# SCH_06_Filter.net
KiCad netlist of a schematic drawn in Altium Designer
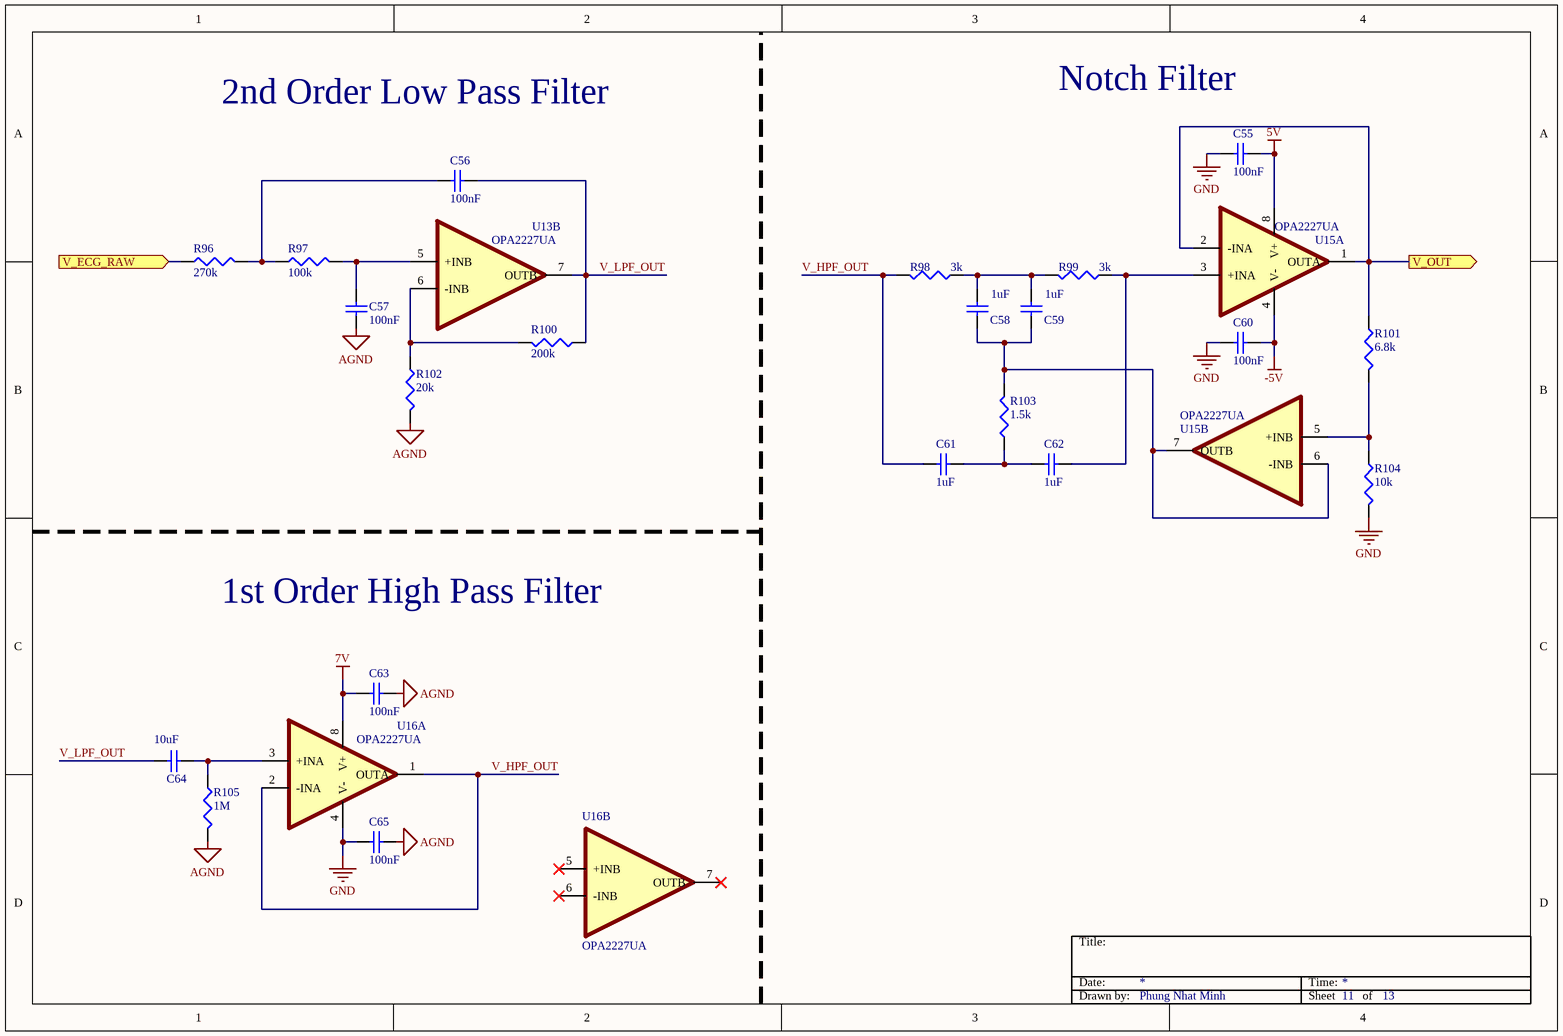
[diagram p0: SCH_06_Filter.SchDoc]

(export (version "E")
  (design (tool "Eeschema 10.0.6"))
  (components
    (comp (ref "C55")
      (value "100nF")
      (footprint "WCAP-CSGP_0603_L1.6W0.8H0.8_Reflow")
      (description "WCAP-CSGP Multilayer Ceramic Chip Capacitor, General Purpose, size 0603, X7R, 100nF, 16VDC")
      (fields
        (field (name "MANUFACTURER PART NUMBER") "885012206046")
        (field (name "MANUFACTURER") "Wurth Elektronik")
      )
      (libsource (lib "Altium_WCAP-CSGP (rev24b)") (part "885012206046"))
    )
    (comp (ref "C56")
      (value "100nF")
      (footprint "WCAP-CSGP_0603_L1.6W0.8H0.8_Reflow")
      (description "WCAP-CSGP Multilayer Ceramic Chip Capacitor, General Purpose, size 0603, X7R, 100nF, 50VDC")
      (fields
        (field (name "MANUFACTURER PART NUMBER") "885012206095")
        (field (name "MANUFACTURER") "Wurth Elektronik")
      )
      (libsource (lib "Altium_WCAP-CSGP (rev24b)") (part "885012206095"))
    )
    (comp (ref "C57")
      (value "100nF")
      (footprint "WCAP-CSGP_0603_L1.6W0.8H0.8_Reflow")
      (description "WCAP-CSGP Multilayer Ceramic Chip Capacitor, General Purpose, size 0603, X7R, 100nF, 50VDC")
      (fields
        (field (name "MANUFACTURER PART NUMBER") "885012206095")
        (field (name "MANUFACTURER") "Wurth Elektronik")
      )
      (libsource (lib "Altium_WCAP-CSGP (rev24b)") (part "885012206095"))
    )
    (comp (ref "C58")
      (value "1uF")
      (footprint "WCAP-CSGP_0603_L1.6W0.8H0.8_Reflow")
      (description "WCAP-CSGP Multilayer Ceramic Chip Capacitor, General Purpose, size 0603, X5R, 1uF, 25VDC")
      (fields
        (field (name "MANUFACTURER PART NUMBER") "885012106022")
        (field (name "MANUFACTURER") "Wurth Elektronik")
      )
      (libsource (lib "Altium_WCAP-CSGP (rev24b)") (part "885012106022"))
    )
    (comp (ref "C59")
      (value "1uF")
      (footprint "WCAP-CSGP_0603_L1.6W0.8H0.8_Reflow")
      (description "WCAP-CSGP Multilayer Ceramic Chip Capacitor, General Purpose, size 0603, X5R, 1uF, 25VDC")
      (fields
        (field (name "MANUFACTURER PART NUMBER") "885012106022")
        (field (name "MANUFACTURER") "Wurth Elektronik")
      )
      (libsource (lib "Altium_WCAP-CSGP (rev24b)") (part "885012106022"))
    )
    (comp (ref "C60")
      (value "100nF")
      (footprint "WCAP-CSGP_0603_L1.6W0.8H0.8_Reflow")
      (description "WCAP-CSGP Multilayer Ceramic Chip Capacitor, General Purpose, size 0603, X7R, 100nF, 16VDC")
      (fields
        (field (name "MANUFACTURER PART NUMBER") "885012206046")
        (field (name "MANUFACTURER") "Wurth Elektronik")
      )
      (libsource (lib "Altium_WCAP-CSGP (rev24b)") (part "885012206046"))
    )
    (comp (ref "C61")
      (value "1uF")
      (footprint "WCAP-CSGP_0603_L1.6W0.8H0.8_Reflow")
      (description "WCAP-CSGP Multilayer Ceramic Chip Capacitor, General Purpose, size 0603, X5R, 1uF, 25VDC")
      (fields
        (field (name "MANUFACTURER PART NUMBER") "885012106022")
        (field (name "MANUFACTURER") "Wurth Elektronik")
      )
      (libsource (lib "Altium_WCAP-CSGP (rev24b)") (part "885012106022"))
    )
    (comp (ref "C62")
      (value "1uF")
      (footprint "WCAP-CSGP_0603_L1.6W0.8H0.8_Reflow")
      (description "WCAP-CSGP Multilayer Ceramic Chip Capacitor, General Purpose, size 0603, X5R, 1uF, 25VDC")
      (fields
        (field (name "MANUFACTURER PART NUMBER") "885012106022")
        (field (name "MANUFACTURER") "Wurth Elektronik")
      )
      (libsource (lib "Altium_WCAP-CSGP (rev24b)") (part "885012106022"))
    )
    (comp (ref "C63")
      (value "100nF")
      (footprint "WCAP-CSGP_0603_L1.6W0.8H0.8_Reflow")
      (description "WCAP-CSGP Multilayer Ceramic Chip Capacitor, General Purpose, size 0603, X7R, 100nF, 50VDC")
      (fields
        (field (name "MANUFACTURER PART NUMBER") "885012206095")
        (field (name "MANUFACTURER") "Wurth Elektronik")
      )
      (libsource (lib "Altium_WCAP-CSGP (rev24b)") (part "885012206095"))
    )
    (comp (ref "C64")
      (value "10uF")
      (footprint "WCAP-CSGP_0603_L1.6W0.8H0.8_Reflow")
      (description "WCAP-CSGP Multilayer Ceramic Chip Capacitor, General Purpose, size 0603, X5R, 10uF, 25VDC")
      (fields
        (field (name "MANUFACTURER PART NUMBER") "885012106031")
        (field (name "MANUFACTURER") "Wurth Elektronik")
      )
      (libsource (lib "Altium_WCAP-CSGP (rev24b)") (part "885012106031"))
    )
    (comp (ref "C65")
      (value "100nF")
      (footprint "WCAP-CSGP_0603_L1.6W0.8H0.8_Reflow")
      (description "WCAP-CSGP Multilayer Ceramic Chip Capacitor, General Purpose, size 0603, X7R, 100nF, 50VDC")
      (fields
        (field (name "MANUFACTURER PART NUMBER") "885012206095")
        (field (name "MANUFACTURER") "Wurth Elektronik")
      )
      (libsource (lib "Altium_WCAP-CSGP (rev24b)") (part "885012206095"))
    )
    (comp (ref "R96")
      (value "270k")
      (footprint "WRIS-PSMB_0603_L1.6W0.8H0.35")
      (description "WRIS-PSMB Metal Plate Resistor, SMT, size 0603, 0.33W, 5mΩ, +/-1%")
      (fields
        (field (name "MANUFACTURER PART NUMBER") "580060716001")
        (field (name "MANUFACTURER") "Wurth Elektronik")
      )
      (libsource (lib "Altium_WRIS-PSMB (rev22a)") (part "580060716001"))
    )
    (comp (ref "R97")
      (value "100k")
      (footprint "WRIS-PSMB_0603_L1.6W0.8H0.35")
      (description "WRIS-PSMB Metal Plate Resistor, SMT, size 0603, 0.33W, 5mΩ, +/-1%")
      (fields
        (field (name "MANUFACTURER PART NUMBER") "580060716001")
        (field (name "MANUFACTURER") "Wurth Elektronik")
      )
      (libsource (lib "Altium_WRIS-PSMB (rev22a)") (part "580060716001"))
    )
    (comp (ref "R98")
      (value "3k")
      (footprint "WRIS-PSMB_0603_L1.6W0.8H0.35")
      (description "WRIS-PSMB Metal Plate Resistor, SMT, size 0603, 0.33W, 5mΩ, +/-1%")
      (fields
        (field (name "MANUFACTURER PART NUMBER") "580060716001")
        (field (name "MANUFACTURER") "Wurth Elektronik")
      )
      (libsource (lib "Altium_WRIS-PSMB (rev22a)") (part "580060716001"))
    )
    (comp (ref "R99")
      (value "3k")
      (footprint "WRIS-PSMB_0603_L1.6W0.8H0.35")
      (description "WRIS-PSMB Metal Plate Resistor, SMT, size 0603, 0.33W, 5mΩ, +/-1%")
      (fields
        (field (name "MANUFACTURER PART NUMBER") "580060716001")
        (field (name "MANUFACTURER") "Wurth Elektronik")
      )
      (libsource (lib "Altium_WRIS-PSMB (rev22a)") (part "580060716001"))
    )
    (comp (ref "R100")
      (value "200k")
      (footprint "WRIS-PSMB_0603_L1.6W0.8H0.35")
      (description "WRIS-PSMB Metal Plate Resistor, SMT, size 0603, 0.33W, 5mΩ, +/-1%")
      (fields
        (field (name "MANUFACTURER PART NUMBER") "580060716001")
        (field (name "MANUFACTURER") "Wurth Elektronik")
      )
      (libsource (lib "Altium_WRIS-PSMB (rev22a)") (part "580060716001"))
    )
    (comp (ref "R101")
      (value "6.8k")
      (footprint "WRIS-PSMB_0603_L1.6W0.8H0.35")
      (description "WRIS-PSMB Metal Plate Resistor, SMT, size 0603, 0.33W, 5mΩ, +/-1%")
      (fields
        (field (name "MANUFACTURER PART NUMBER") "580060716001")
        (field (name "MANUFACTURER") "Wurth Elektronik")
      )
      (libsource (lib "Altium_WRIS-PSMB (rev22a)") (part "580060716001"))
    )
    (comp (ref "R102")
      (value "20k")
      (footprint "WRIS-PSMB_0603_L1.6W0.8H0.35")
      (description "WRIS-PSMB Metal Plate Resistor, SMT, size 0603, 0.33W, 5mΩ, +/-1%")
      (fields
        (field (name "MANUFACTURER PART NUMBER") "580060716001")
        (field (name "MANUFACTURER") "Wurth Elektronik")
      )
      (libsource (lib "Altium_WRIS-PSMB (rev22a)") (part "580060716001"))
    )
    (comp (ref "R103")
      (value "1.5k")
      (footprint "WRIS-PSMB_0603_L1.6W0.8H0.35")
      (description "WRIS-PSMB Metal Plate Resistor, SMT, size 0603, 0.33W, 5mΩ, +/-1%")
      (fields
        (field (name "MANUFACTURER PART NUMBER") "580060716001")
        (field (name "MANUFACTURER") "Wurth Elektronik")
      )
      (libsource (lib "Altium_WRIS-PSMB (rev22a)") (part "580060716001"))
    )
    (comp (ref "R104")
      (value "10k")
      (footprint "WRIS-PSMB_0603_L1.6W0.8H0.35")
      (description "WRIS-PSMB Metal Plate Resistor, SMT, size 0603, 0.33W, 5mΩ, +/-1%")
      (fields
        (field (name "MANUFACTURER PART NUMBER") "580060716001")
        (field (name "MANUFACTURER") "Wurth Elektronik")
      )
      (libsource (lib "Altium_WRIS-PSMB (rev22a)") (part "580060716001"))
    )
    (comp (ref "R105")
      (value "1M")
      (footprint "WRIS-PSMB_0603_L1.6W0.8H0.35")
      (description "WRIS-PSMB Metal Plate Resistor, SMT, size 0603, 0.33W, 5mΩ, +/-1%")
      (fields
        (field (name "MANUFACTURER PART NUMBER") "580060716001")
        (field (name "MANUFACTURER") "Wurth Elektronik")
      )
      (libsource (lib "Altium_WRIS-PSMB (rev22a)") (part "580060716001"))
    )
    (comp (ref "U13")
      (value "OPA2227UA")
      (footprint "SOIC127P599X175-8N")
      (libsource (lib "OPA2277UA") (part "OPA2227UA"))
    )
    (comp (ref "U15")
      (value "OPA2227UA")
      (footprint "SOIC127P599X175-8N")
      (libsource (lib "OPA2227UA") (part "OPA2227UA"))
    )
    (comp (ref "U16")
      (value "OPA2227UA")
      (footprint "SOIC127P599X175-8N")
      (libsource (lib "OPA2277UA") (part "OPA2227UA"))
    )
  )
  (nets
    (net (code "1") (name "-5V") (class "Default")
      (node (ref "C60") (pin "2") (pinfunction "2_2") (pintype "passive"))
      (node (ref "U15") (pin "4") (pinfunction "V-_4") (pintype "power_in"))
    )
    (net (code "2") (name "/V_ECG_RAW") (class "Default")
      (node (ref "R96") (pin "1") (pinfunction "1_1") (pintype "passive"))
    )
    (net (code "3") (name "/V_HPF_OUT") (class "Default")
      (node (ref "C61") (pin "2") (pinfunction "2_2") (pintype "passive"))
      (node (ref "R98") (pin "2") (pinfunction "2_2") (pintype "passive"))
      (node (ref "U16") (pin "1") (pinfunction "OUTA_1") (pintype "passive"))
      (node (ref "U16") (pin "2") (pinfunction "-INA_2") (pintype "passive"))
    )
    (net (code "4") (name "/V_LPF_OUT") (class "Default")
      (node (ref "C56") (pin "1") (pinfunction "1_1") (pintype "passive"))
      (node (ref "C64") (pin "1") (pinfunction "1_1") (pintype "passive"))
      (node (ref "R100") (pin "1") (pinfunction "1_1") (pintype "passive"))
      (node (ref "U13") (pin "7") (pinfunction "OUTB_7") (pintype "passive"))
    )
    (net (code "5") (name "/V_OUT") (class "Default")
      (node (ref "R101") (pin "1") (pinfunction "1_1") (pintype "passive"))
      (node (ref "U15") (pin "1") (pinfunction "OUTA_1") (pintype "passive"))
      (node (ref "U15") (pin "2") (pinfunction "-INA_2") (pintype "passive"))
    )
    (net (code "6") (name "5V") (class "Default")
      (node (ref "C55") (pin "2") (pinfunction "2_2") (pintype "passive"))
      (node (ref "U15") (pin "8") (pinfunction "V+_8") (pintype "power_in"))
    )
    (net (code "7") (name "7V") (class "Default")
      (node (ref "C63") (pin "2") (pinfunction "2_2") (pintype "passive"))
      (node (ref "U16") (pin "8") (pinfunction "V+_8") (pintype "power_in"))
    )
    (net (code "8") (name "AGND") (class "Default")
      (node (ref "C57") (pin "1") (pinfunction "1_1") (pintype "passive"))
      (node (ref "C63") (pin "1") (pinfunction "1_1") (pintype "passive"))
      (node (ref "C65") (pin "1") (pinfunction "1_1") (pintype "passive"))
      (node (ref "R102") (pin "2") (pinfunction "2_2") (pintype "passive"))
      (node (ref "R105") (pin "2") (pinfunction "2_2") (pintype "passive"))
    )
    (net (code "9") (name "GND") (class "Default")
      (node (ref "C55") (pin "1") (pinfunction "1_1") (pintype "passive"))
      (node (ref "C60") (pin "1") (pinfunction "1_1") (pintype "passive"))
      (node (ref "C65") (pin "2") (pinfunction "2_2") (pintype "passive"))
      (node (ref "R104") (pin "2") (pinfunction "2_2") (pintype "passive"))
      (node (ref "U16") (pin "4") (pinfunction "V-_4") (pintype "power_in"))
    )
    (net (code "10") (name "Net-(C56-Pad2)") (class "Default")
      (node (ref "C56") (pin "2") (pinfunction "2_2") (pintype "passive"))
      (node (ref "R96") (pin "2") (pinfunction "2_2") (pintype "passive"))
      (node (ref "R97") (pin "1") (pinfunction "1_1") (pintype "passive"))
    )
    (net (code "11") (name "Net-(C58-Pad2)") (class "Default")
      (node (ref "C58") (pin "2") (pinfunction "2_2") (pintype "passive"))
      (node (ref "C59") (pin "2") (pinfunction "2_2") (pintype "passive"))
      (node (ref "R98") (pin "1") (pinfunction "1_1") (pintype "passive"))
      (node (ref "R99") (pin "2") (pinfunction "2_2") (pintype "passive"))
    )
    (net (code "12") (name "Net-(C61-Pad1)") (class "Default")
      (node (ref "C61") (pin "1") (pinfunction "1_1") (pintype "passive"))
      (node (ref "C62") (pin "2") (pinfunction "2_2") (pintype "passive"))
      (node (ref "R103") (pin "1") (pinfunction "1_1") (pintype "passive"))
    )
    (net (code "13") (name "Net-(U13B-+INB)") (class "Default")
      (node (ref "C57") (pin "2") (pinfunction "2_2") (pintype "passive"))
      (node (ref "R97") (pin "2") (pinfunction "2_2") (pintype "passive"))
      (node (ref "U13") (pin "5") (pinfunction "+INB_5") (pintype "passive"))
    )
    (net (code "14") (name "Net-(U13B--INB)") (class "Default")
      (node (ref "R100") (pin "2") (pinfunction "2_2") (pintype "passive"))
      (node (ref "R102") (pin "1") (pinfunction "1_1") (pintype "passive"))
      (node (ref "U13") (pin "6") (pinfunction "-INB_6") (pintype "passive"))
    )
    (net (code "15") (name "Net-(U15A-+INA)") (class "Default")
      (node (ref "C62") (pin "1") (pinfunction "1_1") (pintype "passive"))
      (node (ref "R99") (pin "1") (pinfunction "1_1") (pintype "passive"))
      (node (ref "U15") (pin "3") (pinfunction "+INA_3") (pintype "passive"))
    )
    (net (code "16") (name "Net-(U15B-+INB)") (class "Default")
      (node (ref "R101") (pin "2") (pinfunction "2_2") (pintype "passive"))
      (node (ref "R104") (pin "1") (pinfunction "1_1") (pintype "passive"))
      (node (ref "U15") (pin "5") (pinfunction "+INB_5") (pintype "passive"))
    )
    (net (code "17") (name "Net-(U15B--INB)") (class "Default")
      (node (ref "C58") (pin "1") (pinfunction "1_1") (pintype "passive"))
      (node (ref "C59") (pin "1") (pinfunction "1_1") (pintype "passive"))
      (node (ref "R103") (pin "2") (pinfunction "2_2") (pintype "passive"))
      (node (ref "U15") (pin "6") (pinfunction "-INB_6") (pintype "passive"))
      (node (ref "U15") (pin "7") (pinfunction "OUTB_7") (pintype "passive"))
    )
    (net (code "18") (name "Net-(U16A-+INA)") (class "Default")
      (node (ref "C64") (pin "2") (pinfunction "2_2") (pintype "passive"))
      (node (ref "R105") (pin "1") (pinfunction "1_1") (pintype "passive"))
      (node (ref "U16") (pin "3") (pinfunction "+INA_3") (pintype "passive"))
    )
    (net (code "19") (name "unconnected-(U16B-+INB-Pad5)") (class "Default")
      (node (ref "U16") (pin "5") (pinfunction "+INB_5") (pintype "passive+no_connect"))
    )
    (net (code "20") (name "unconnected-(U16B--INB-Pad6)") (class "Default")
      (node (ref "U16") (pin "6") (pinfunction "-INB_6") (pintype "passive+no_connect"))
    )
    (net (code "21") (name "unconnected-(U16B-OUTB-Pad7)") (class "Default")
      (node (ref "U16") (pin "7") (pinfunction "OUTB_7") (pintype "passive+no_connect"))
    )
  )
)
